# 5x5_Led_Matrix.net
KiCad netlist of a schematic drawn in EAGLE
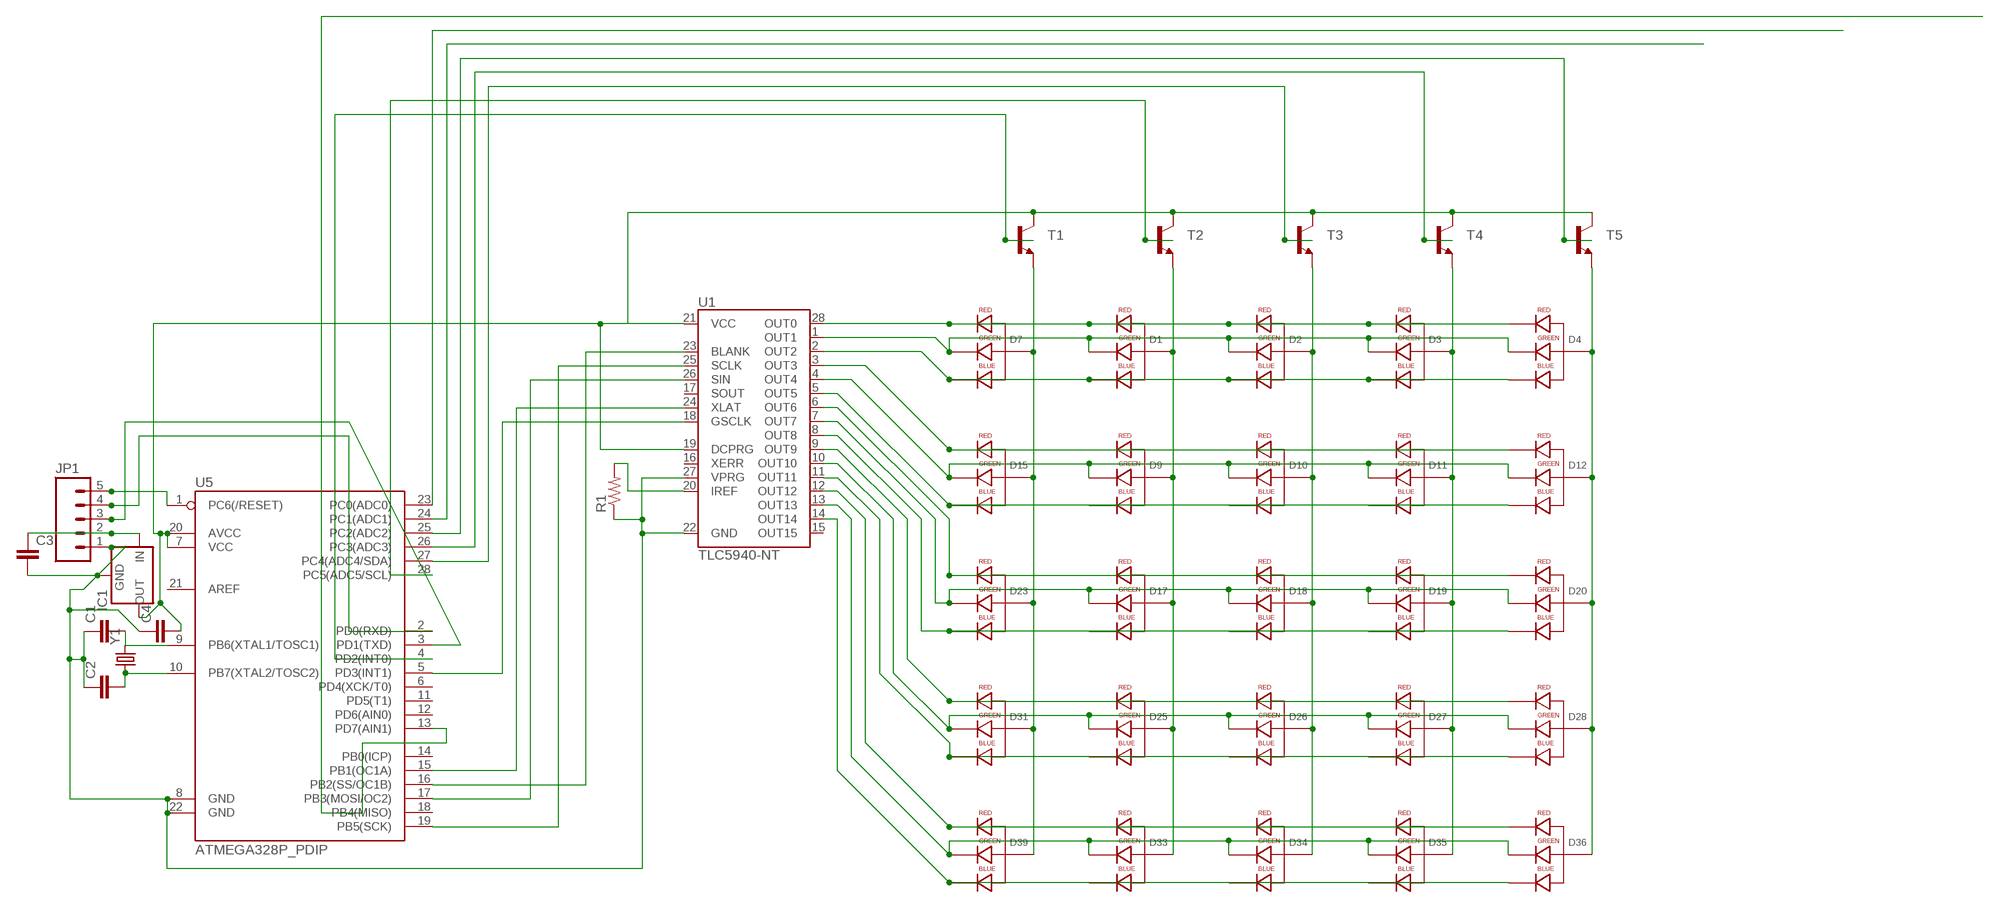
[diagram p0: schematic, sheet 1]

(export (version "E")
  (design (tool "Eeschema 10.0.6"))
  (components
    (comp (ref "C1")
      (value "CAPPTH")
      (footprint "eagle-import:CAP-PTH-SMALL")
      (libsource (lib "eagle-import") (part "CAPPTH"))
    )
    (comp (ref "C2")
      (value "CAPPTH")
      (footprint "eagle-import:CAP-PTH-SMALL")
      (libsource (lib "eagle-import") (part "CAPPTH"))
    )
    (comp (ref "C3")
      (value "CAPPTH")
      (footprint "eagle-import:CAP-PTH-SMALL")
      (libsource (lib "eagle-import") (part "SparkFun-Passives_CAPPTH"))
    )
    (comp (ref "C4")
      (value "CAPPTH")
      (footprint "eagle-import:CAP-PTH-SMALL")
      (libsource (lib "eagle-import") (part "SparkFun-Passives_CAPPTH"))
    )
    (comp (ref "D1")
      (value "LED-RGB-CA-THRUDIFFUSE")
      (footprint "eagle-import:LED-RGB-THRU")
      (libsource (lib "eagle-import") (part "LED-RGB-CA-THRUDIFFUSE"))
    )
    (comp (ref "D2")
      (value "LED-RGB-CA-THRUDIFFUSE")
      (footprint "eagle-import:LED-RGB-THRU")
      (libsource (lib "eagle-import") (part "LED-RGB-CA-THRUDIFFUSE"))
    )
    (comp (ref "D3")
      (value "LED-RGB-CA-THRUDIFFUSE")
      (footprint "eagle-import:LED-RGB-THRU")
      (libsource (lib "eagle-import") (part "LED-RGB-CA-THRUDIFFUSE"))
    )
    (comp (ref "D4")
      (value "LED-RGB-CA-THRUDIFFUSE")
      (footprint "eagle-import:LED-RGB-THRU")
      (libsource (lib "eagle-import") (part "LED-RGB-CA-THRUDIFFUSE"))
    )
    (comp (ref "D7")
      (value "LED-RGB-CA-THRUCLEAR")
      (footprint "eagle-import:LED-RGB-THRU")
      (libsource (lib "eagle-import") (part "LED-RGB-CA-THRUCLEAR"))
    )
    (comp (ref "D9")
      (value "LED-RGB-CA-THRUDIFFUSE")
      (footprint "eagle-import:LED-RGB-THRU")
      (libsource (lib "eagle-import") (part "LED-RGB-CA-THRUDIFFUSE"))
    )
    (comp (ref "D10")
      (value "LED-RGB-CA-THRUDIFFUSE")
      (footprint "eagle-import:LED-RGB-THRU")
      (libsource (lib "eagle-import") (part "LED-RGB-CA-THRUDIFFUSE"))
    )
    (comp (ref "D11")
      (value "LED-RGB-CA-THRUDIFFUSE")
      (footprint "eagle-import:LED-RGB-THRU")
      (libsource (lib "eagle-import") (part "LED-RGB-CA-THRUDIFFUSE"))
    )
    (comp (ref "D12")
      (value "LED-RGB-CA-THRUDIFFUSE")
      (footprint "eagle-import:LED-RGB-THRU")
      (libsource (lib "eagle-import") (part "LED-RGB-CA-THRUDIFFUSE"))
    )
    (comp (ref "D15")
      (value "LED-RGB-CA-THRUDIFFUSE")
      (footprint "eagle-import:LED-RGB-THRU")
      (libsource (lib "eagle-import") (part "LED-RGB-CA-THRUDIFFUSE"))
    )
    (comp (ref "D17")
      (value "LED-RGB-CA-THRUDIFFUSE")
      (footprint "eagle-import:LED-RGB-THRU")
      (libsource (lib "eagle-import") (part "LED-RGB-CA-THRUDIFFUSE"))
    )
    (comp (ref "D18")
      (value "LED-RGB-CA-THRUDIFFUSE")
      (footprint "eagle-import:LED-RGB-THRU")
      (libsource (lib "eagle-import") (part "LED-RGB-CA-THRUDIFFUSE"))
    )
    (comp (ref "D19")
      (value "LED-RGB-CA-THRUDIFFUSE")
      (footprint "eagle-import:LED-RGB-THRU")
      (libsource (lib "eagle-import") (part "LED-RGB-CA-THRUDIFFUSE"))
    )
    (comp (ref "D20")
      (value "LED-RGB-CA-THRUDIFFUSE")
      (footprint "eagle-import:LED-RGB-THRU")
      (libsource (lib "eagle-import") (part "LED-RGB-CA-THRUDIFFUSE"))
    )
    (comp (ref "D23")
      (value "LED-RGB-CA-THRUDIFFUSE")
      (footprint "eagle-import:LED-RGB-THRU")
      (libsource (lib "eagle-import") (part "LED-RGB-CA-THRUDIFFUSE"))
    )
    (comp (ref "D25")
      (value "LED-RGB-CA-THRUDIFFUSE")
      (footprint "eagle-import:LED-RGB-THRU")
      (libsource (lib "eagle-import") (part "LED-RGB-CA-THRUDIFFUSE"))
    )
    (comp (ref "D26")
      (value "LED-RGB-CA-THRUDIFFUSE")
      (footprint "eagle-import:LED-RGB-THRU")
      (libsource (lib "eagle-import") (part "LED-RGB-CA-THRUDIFFUSE"))
    )
    (comp (ref "D27")
      (value "LED-RGB-CA-THRUDIFFUSE")
      (footprint "eagle-import:LED-RGB-THRU")
      (libsource (lib "eagle-import") (part "LED-RGB-CA-THRUDIFFUSE"))
    )
    (comp (ref "D28")
      (value "LED-RGB-CA-THRUCLEAR")
      (footprint "eagle-import:LED-RGB-THRU")
      (libsource (lib "eagle-import") (part "LED-RGB-CA-THRUCLEAR"))
    )
    (comp (ref "D31")
      (value "LED-RGB-CA-THRUDIFFUSE")
      (footprint "eagle-import:LED-RGB-THRU")
      (libsource (lib "eagle-import") (part "LED-RGB-CA-THRUDIFFUSE"))
    )
    (comp (ref "D33")
      (value "LED-RGB-CA-THRUDIFFUSE")
      (footprint "eagle-import:LED-RGB-THRU")
      (libsource (lib "eagle-import") (part "LED-RGB-CA-THRUDIFFUSE"))
    )
    (comp (ref "D34")
      (value "LED-RGB-CA-THRUDIFFUSE")
      (footprint "eagle-import:LED-RGB-THRU")
      (libsource (lib "eagle-import") (part "LED-RGB-CA-THRUDIFFUSE"))
    )
    (comp (ref "D35")
      (value "LED-RGB-CA-THRUDIFFUSE")
      (footprint "eagle-import:LED-RGB-THRU")
      (libsource (lib "eagle-import") (part "LED-RGB-CA-THRUDIFFUSE"))
    )
    (comp (ref "D36")
      (value "LED-RGB-CA-THRUDIFFUSE")
      (footprint "eagle-import:LED-RGB-THRU")
      (libsource (lib "eagle-import") (part "LED-RGB-CA-THRUDIFFUSE"))
    )
    (comp (ref "D39")
      (value "LED-RGB-CA-THRUDIFFUSE")
      (footprint "eagle-import:LED-RGB-THRU")
      (libsource (lib "eagle-import") (part "LED-RGB-CA-THRUDIFFUSE"))
    )
    (comp (ref "IC1")
      (value "V_REG_78XXSIDE")
      (footprint "eagle-import:78XXL")
      (libsource (lib "eagle-import") (part "V_REG_78XXSIDE"))
    )
    (comp (ref "JP1")
      (value "M05PTH")
      (footprint "eagle-import:1X05")
      (libsource (lib "eagle-import") (part "M05PTH"))
    )
    (comp (ref "R1")
      (value "RESISTORPTH-1/2W")
      (footprint "eagle-import:AXIAL-0.5")
      (libsource (lib "eagle-import") (part "RESISTORPTH-1/2W"))
    )
    (comp (ref "T1")
      (value "TRANSISTOR_NPN2N3904")
      (footprint "eagle-import:TO-92")
      (libsource (lib "eagle-import") (part "TRANSISTOR_NPN2N3904"))
    )
    (comp (ref "T2")
      (value "TRANSISTOR_NPN2N3904")
      (footprint "eagle-import:TO-92")
      (libsource (lib "eagle-import") (part "TRANSISTOR_NPN2N3904"))
    )
    (comp (ref "T3")
      (value "TRANSISTOR_NPN2N3904")
      (footprint "eagle-import:TO-92")
      (libsource (lib "eagle-import") (part "TRANSISTOR_NPN2N3904"))
    )
    (comp (ref "T4")
      (value "TRANSISTOR_NPN2N3904")
      (footprint "eagle-import:TO-92")
      (libsource (lib "eagle-import") (part "TRANSISTOR_NPN2N3904"))
    )
    (comp (ref "T5")
      (value "TRANSISTOR_NPN2N3904")
      (footprint "eagle-import:TO-92")
      (libsource (lib "eagle-import") (part "TRANSISTOR_NPN2N3904"))
    )
    (comp (ref "U1")
      (value "TLC5940-NT")
      (footprint "eagle-import:DIL28-3")
      (libsource (lib "eagle-import") (part "TLC5940-NT"))
    )
    (comp (ref "U5")
      (value "ATMEGA328P_PDIP")
      (footprint "eagle-import:DIL28-3")
      (libsource (lib "eagle-import") (part "ATMEGA328P_PDIP"))
    )
    (comp (ref "Y1")
      (value "CRYSTALHC49US")
      (footprint "eagle-import:HC49US")
      (libsource (lib "eagle-import") (part "CRYSTALHC49US"))
    )
  )
  (nets
    (net (code "1") (name "Net-(C3-Pad1)") (class "Default")
      (node (ref "C3") (pin "1") (pinfunction "1_1") (pintype "passive"))
      (node (ref "IC1") (pin "IN") (pinfunction "IN_IN") (pintype "input"))
      (node (ref "JP1") (pin "2") (pinfunction "2_2") (pintype "passive"))
    )
    (net (code "2") (name "Net-(D1-ANODE)") (class "Default")
      (node (ref "D1") (pin "2") (pinfunction "ANODE_2") (pintype "bidirectional"))
      (node (ref "D17") (pin "2") (pinfunction "ANODE_2") (pintype "bidirectional"))
      (node (ref "D25") (pin "2") (pinfunction "ANODE_2") (pintype "bidirectional"))
      (node (ref "D33") (pin "2") (pinfunction "ANODE_2") (pintype "bidirectional"))
      (node (ref "D9") (pin "2") (pinfunction "ANODE_2") (pintype "bidirectional"))
      (node (ref "T2") (pin "1") (pinfunction "E_1") (pintype "passive"))
    )
    (net (code "3") (name "Net-(D1-BLUE_CATHODE)") (class "Default")
      (node (ref "D1") (pin "4") (pinfunction "BLUE_CATHODE_4") (pintype "bidirectional"))
      (node (ref "D2") (pin "4") (pinfunction "BLUE_CATHODE_4") (pintype "bidirectional"))
      (node (ref "D3") (pin "4") (pinfunction "BLUE_CATHODE_4") (pintype "bidirectional"))
      (node (ref "D4") (pin "4") (pinfunction "BLUE_CATHODE_4") (pintype "bidirectional"))
      (node (ref "D7") (pin "4") (pinfunction "BLUE_CATHODE_4") (pintype "bidirectional"))
      (node (ref "U1") (pin "2") (pinfunction "OUT2_2") (pintype "bidirectional"))
    )
    (net (code "4") (name "Net-(D1-GREEN_CATHODE)") (class "Default")
      (node (ref "D1") (pin "3") (pinfunction "GREEN_CATHODE_3") (pintype "bidirectional"))
      (node (ref "D2") (pin "3") (pinfunction "GREEN_CATHODE_3") (pintype "bidirectional"))
      (node (ref "D3") (pin "3") (pinfunction "GREEN_CATHODE_3") (pintype "bidirectional"))
      (node (ref "D4") (pin "3") (pinfunction "GREEN_CATHODE_3") (pintype "bidirectional"))
      (node (ref "D7") (pin "3") (pinfunction "GREEN_CATHODE_3") (pintype "bidirectional"))
      (node (ref "U1") (pin "1") (pinfunction "OUT1_1") (pintype "bidirectional"))
    )
    (net (code "5") (name "Net-(D1-RED_CATHODE)") (class "Default")
      (node (ref "D1") (pin "1") (pinfunction "RED_CATHODE_1") (pintype "bidirectional"))
      (node (ref "D2") (pin "1") (pinfunction "RED_CATHODE_1") (pintype "bidirectional"))
      (node (ref "D3") (pin "1") (pinfunction "RED_CATHODE_1") (pintype "bidirectional"))
      (node (ref "D4") (pin "1") (pinfunction "RED_CATHODE_1") (pintype "bidirectional"))
      (node (ref "D7") (pin "1") (pinfunction "RED_CATHODE_1") (pintype "bidirectional"))
      (node (ref "U1") (pin "28") (pinfunction "OUT0_28") (pintype "bidirectional"))
    )
    (net (code "6") (name "Net-(D10-ANODE)") (class "Default")
      (node (ref "D10") (pin "2") (pinfunction "ANODE_2") (pintype "bidirectional"))
      (node (ref "D18") (pin "2") (pinfunction "ANODE_2") (pintype "bidirectional"))
      (node (ref "D2") (pin "2") (pinfunction "ANODE_2") (pintype "bidirectional"))
      (node (ref "D26") (pin "2") (pinfunction "ANODE_2") (pintype "bidirectional"))
      (node (ref "D34") (pin "2") (pinfunction "ANODE_2") (pintype "bidirectional"))
      (node (ref "T3") (pin "1") (pinfunction "E_1") (pintype "passive"))
    )
    (net (code "7") (name "Net-(D10-BLUE_CATHODE)") (class "Default")
      (node (ref "D10") (pin "4") (pinfunction "BLUE_CATHODE_4") (pintype "bidirectional"))
      (node (ref "D11") (pin "4") (pinfunction "BLUE_CATHODE_4") (pintype "bidirectional"))
      (node (ref "D12") (pin "4") (pinfunction "BLUE_CATHODE_4") (pintype "bidirectional"))
      (node (ref "D15") (pin "4") (pinfunction "BLUE_CATHODE_4") (pintype "bidirectional"))
      (node (ref "D9") (pin "4") (pinfunction "BLUE_CATHODE_4") (pintype "bidirectional"))
      (node (ref "U1") (pin "5") (pinfunction "OUT5_5") (pintype "bidirectional"))
    )
    (net (code "8") (name "Net-(D10-GREEN_CATHODE)") (class "Default")
      (node (ref "D10") (pin "3") (pinfunction "GREEN_CATHODE_3") (pintype "bidirectional"))
      (node (ref "D11") (pin "3") (pinfunction "GREEN_CATHODE_3") (pintype "bidirectional"))
      (node (ref "D12") (pin "3") (pinfunction "GREEN_CATHODE_3") (pintype "bidirectional"))
      (node (ref "D15") (pin "3") (pinfunction "GREEN_CATHODE_3") (pintype "bidirectional"))
      (node (ref "D9") (pin "3") (pinfunction "GREEN_CATHODE_3") (pintype "bidirectional"))
      (node (ref "U1") (pin "4") (pinfunction "OUT4_4") (pintype "bidirectional"))
    )
    (net (code "9") (name "Net-(D10-RED_CATHODE)") (class "Default")
      (node (ref "D10") (pin "1") (pinfunction "RED_CATHODE_1") (pintype "bidirectional"))
      (node (ref "D11") (pin "1") (pinfunction "RED_CATHODE_1") (pintype "bidirectional"))
      (node (ref "D12") (pin "1") (pinfunction "RED_CATHODE_1") (pintype "bidirectional"))
      (node (ref "D15") (pin "1") (pinfunction "RED_CATHODE_1") (pintype "bidirectional"))
      (node (ref "D9") (pin "1") (pinfunction "RED_CATHODE_1") (pintype "bidirectional"))
      (node (ref "U1") (pin "3") (pinfunction "OUT3_3") (pintype "bidirectional"))
    )
    (net (code "10") (name "Net-(D11-ANODE)") (class "Default")
      (node (ref "D11") (pin "2") (pinfunction "ANODE_2") (pintype "bidirectional"))
      (node (ref "D19") (pin "2") (pinfunction "ANODE_2") (pintype "bidirectional"))
      (node (ref "D27") (pin "2") (pinfunction "ANODE_2") (pintype "bidirectional"))
      (node (ref "D3") (pin "2") (pinfunction "ANODE_2") (pintype "bidirectional"))
      (node (ref "D35") (pin "2") (pinfunction "ANODE_2") (pintype "bidirectional"))
      (node (ref "T4") (pin "1") (pinfunction "E_1") (pintype "passive"))
    )
    (net (code "11") (name "Net-(D12-ANODE)") (class "Default")
      (node (ref "D12") (pin "2") (pinfunction "ANODE_2") (pintype "bidirectional"))
      (node (ref "D20") (pin "2") (pinfunction "ANODE_2") (pintype "bidirectional"))
      (node (ref "D28") (pin "2") (pinfunction "ANODE_2") (pintype "bidirectional"))
      (node (ref "D36") (pin "2") (pinfunction "ANODE_2") (pintype "bidirectional"))
      (node (ref "D4") (pin "2") (pinfunction "ANODE_2") (pintype "bidirectional"))
      (node (ref "T5") (pin "1") (pinfunction "E_1") (pintype "passive"))
    )
    (net (code "12") (name "Net-(D15-ANODE)") (class "Default")
      (node (ref "D15") (pin "2") (pinfunction "ANODE_2") (pintype "bidirectional"))
      (node (ref "D23") (pin "2") (pinfunction "ANODE_2") (pintype "bidirectional"))
      (node (ref "D31") (pin "2") (pinfunction "ANODE_2") (pintype "bidirectional"))
      (node (ref "D39") (pin "2") (pinfunction "ANODE_2") (pintype "bidirectional"))
      (node (ref "D7") (pin "2") (pinfunction "ANODE_2") (pintype "bidirectional"))
      (node (ref "T1") (pin "1") (pinfunction "E_1") (pintype "passive"))
    )
    (net (code "13") (name "Net-(D17-BLUE_CATHODE)") (class "Default")
      (node (ref "D17") (pin "4") (pinfunction "BLUE_CATHODE_4") (pintype "bidirectional"))
      (node (ref "D18") (pin "4") (pinfunction "BLUE_CATHODE_4") (pintype "bidirectional"))
      (node (ref "D19") (pin "4") (pinfunction "BLUE_CATHODE_4") (pintype "bidirectional"))
      (node (ref "D20") (pin "4") (pinfunction "BLUE_CATHODE_4") (pintype "bidirectional"))
      (node (ref "D23") (pin "4") (pinfunction "BLUE_CATHODE_4") (pintype "bidirectional"))
      (node (ref "U1") (pin "8") (pinfunction "OUT8_8") (pintype "bidirectional"))
    )
    (net (code "14") (name "Net-(D17-GREEN_CATHODE)") (class "Default")
      (node (ref "D17") (pin "3") (pinfunction "GREEN_CATHODE_3") (pintype "bidirectional"))
      (node (ref "D18") (pin "3") (pinfunction "GREEN_CATHODE_3") (pintype "bidirectional"))
      (node (ref "D19") (pin "3") (pinfunction "GREEN_CATHODE_3") (pintype "bidirectional"))
      (node (ref "D20") (pin "3") (pinfunction "GREEN_CATHODE_3") (pintype "bidirectional"))
      (node (ref "D23") (pin "3") (pinfunction "GREEN_CATHODE_3") (pintype "bidirectional"))
      (node (ref "U1") (pin "7") (pinfunction "OUT7_7") (pintype "bidirectional"))
    )
    (net (code "15") (name "Net-(D17-RED_CATHODE)") (class "Default")
      (node (ref "D17") (pin "1") (pinfunction "RED_CATHODE_1") (pintype "bidirectional"))
      (node (ref "D18") (pin "1") (pinfunction "RED_CATHODE_1") (pintype "bidirectional"))
      (node (ref "D19") (pin "1") (pinfunction "RED_CATHODE_1") (pintype "bidirectional"))
      (node (ref "D20") (pin "1") (pinfunction "RED_CATHODE_1") (pintype "bidirectional"))
      (node (ref "D23") (pin "1") (pinfunction "RED_CATHODE_1") (pintype "bidirectional"))
      (node (ref "U1") (pin "6") (pinfunction "OUT6_6") (pintype "bidirectional"))
    )
    (net (code "16") (name "Net-(D25-BLUE_CATHODE)") (class "Default")
      (node (ref "D25") (pin "4") (pinfunction "BLUE_CATHODE_4") (pintype "bidirectional"))
      (node (ref "D26") (pin "4") (pinfunction "BLUE_CATHODE_4") (pintype "bidirectional"))
      (node (ref "D27") (pin "4") (pinfunction "BLUE_CATHODE_4") (pintype "bidirectional"))
      (node (ref "D28") (pin "4") (pinfunction "BLUE_CATHODE_4") (pintype "bidirectional"))
      (node (ref "D31") (pin "4") (pinfunction "BLUE_CATHODE_4") (pintype "bidirectional"))
      (node (ref "U1") (pin "11") (pinfunction "OUT11_11") (pintype "bidirectional"))
    )
    (net (code "17") (name "Net-(D25-GREEN_CATHODE)") (class "Default")
      (node (ref "D25") (pin "3") (pinfunction "GREEN_CATHODE_3") (pintype "bidirectional"))
      (node (ref "D26") (pin "3") (pinfunction "GREEN_CATHODE_3") (pintype "bidirectional"))
      (node (ref "D27") (pin "3") (pinfunction "GREEN_CATHODE_3") (pintype "bidirectional"))
      (node (ref "D28") (pin "3") (pinfunction "GREEN_CATHODE_3") (pintype "bidirectional"))
      (node (ref "D31") (pin "3") (pinfunction "GREEN_CATHODE_3") (pintype "bidirectional"))
      (node (ref "U1") (pin "10") (pinfunction "OUT10_10") (pintype "bidirectional"))
    )
    (net (code "18") (name "Net-(D25-RED_CATHODE)") (class "Default")
      (node (ref "D25") (pin "1") (pinfunction "RED_CATHODE_1") (pintype "bidirectional"))
      (node (ref "D26") (pin "1") (pinfunction "RED_CATHODE_1") (pintype "bidirectional"))
      (node (ref "D27") (pin "1") (pinfunction "RED_CATHODE_1") (pintype "bidirectional"))
      (node (ref "D28") (pin "1") (pinfunction "RED_CATHODE_1") (pintype "bidirectional"))
      (node (ref "D31") (pin "1") (pinfunction "RED_CATHODE_1") (pintype "bidirectional"))
      (node (ref "U1") (pin "9") (pinfunction "OUT9_9") (pintype "bidirectional"))
    )
    (net (code "19") (name "Net-(D33-BLUE_CATHODE)") (class "Default")
      (node (ref "D33") (pin "4") (pinfunction "BLUE_CATHODE_4") (pintype "bidirectional"))
      (node (ref "D34") (pin "4") (pinfunction "BLUE_CATHODE_4") (pintype "bidirectional"))
      (node (ref "D35") (pin "4") (pinfunction "BLUE_CATHODE_4") (pintype "bidirectional"))
      (node (ref "D36") (pin "4") (pinfunction "BLUE_CATHODE_4") (pintype "bidirectional"))
      (node (ref "D39") (pin "4") (pinfunction "BLUE_CATHODE_4") (pintype "bidirectional"))
      (node (ref "U1") (pin "14") (pinfunction "OUT14_14") (pintype "bidirectional"))
    )
    (net (code "20") (name "Net-(D33-GREEN_CATHODE)") (class "Default")
      (node (ref "D33") (pin "3") (pinfunction "GREEN_CATHODE_3") (pintype "bidirectional"))
      (node (ref "D34") (pin "3") (pinfunction "GREEN_CATHODE_3") (pintype "bidirectional"))
      (node (ref "D35") (pin "3") (pinfunction "GREEN_CATHODE_3") (pintype "bidirectional"))
      (node (ref "D36") (pin "3") (pinfunction "GREEN_CATHODE_3") (pintype "bidirectional"))
      (node (ref "D39") (pin "3") (pinfunction "GREEN_CATHODE_3") (pintype "bidirectional"))
      (node (ref "U1") (pin "13") (pinfunction "OUT13_13") (pintype "bidirectional"))
    )
    (net (code "21") (name "Net-(D33-RED_CATHODE)") (class "Default")
      (node (ref "D33") (pin "1") (pinfunction "RED_CATHODE_1") (pintype "bidirectional"))
      (node (ref "D34") (pin "1") (pinfunction "RED_CATHODE_1") (pintype "bidirectional"))
      (node (ref "D35") (pin "1") (pinfunction "RED_CATHODE_1") (pintype "bidirectional"))
      (node (ref "D36") (pin "1") (pinfunction "RED_CATHODE_1") (pintype "bidirectional"))
      (node (ref "D39") (pin "1") (pinfunction "RED_CATHODE_1") (pintype "bidirectional"))
      (node (ref "U1") (pin "12") (pinfunction "OUT12_12") (pintype "bidirectional"))
    )
    (net (code "22") (name "Net-(R1-1)") (class "Default")
      (node (ref "C1") (pin "1") (pinfunction "1_1") (pintype "passive"))
      (node (ref "C2") (pin "1") (pinfunction "1_1") (pintype "passive"))
      (node (ref "C3") (pin "2") (pinfunction "2_2") (pintype "passive"))
      (node (ref "C4") (pin "1") (pinfunction "1_1") (pintype "passive"))
      (node (ref "IC1") (pin "GND") (pinfunction "GND_GND") (pintype "input"))
      (node (ref "JP1") (pin "1") (pinfunction "1_1") (pintype "passive"))
      (node (ref "R1") (pin "P$1") (pinfunction "1_P$1") (pintype "passive"))
      (node (ref "U1") (pin "22") (pinfunction "GND_22") (pintype "bidirectional"))
      (node (ref "U1") (pin "27") (pinfunction "VPRG_27") (pintype "bidirectional"))
      (node (ref "U5") (pin "22") (pinfunction "GND_22") (pintype "bidirectional"))
      (node (ref "U5") (pin "8") (pinfunction "GND_8") (pintype "bidirectional"))
    )
    (net (code "23") (name "Net-(R1-2)") (class "Default")
      (node (ref "R1") (pin "P$2") (pinfunction "2_P$2") (pintype "passive"))
      (node (ref "U1") (pin "20") (pinfunction "IREF_20") (pintype "bidirectional"))
    )
    (net (code "24") (name "Net-(T1-B)") (class "Default")
      (node (ref "T1") (pin "2") (pinfunction "B_2") (pintype "passive"))
      (node (ref "U5") (pin "4") (pinfunction "PD2(INT0)_4") (pintype "bidirectional"))
    )
    (net (code "25") (name "Net-(T1-C)") (class "Default")
      (node (ref "C4") (pin "2") (pinfunction "2_2") (pintype "passive"))
      (node (ref "IC1") (pin "OUT") (pinfunction "OUT_OUT") (pintype "output"))
      (node (ref "T1") (pin "3") (pinfunction "C_3") (pintype "passive"))
      (node (ref "T2") (pin "3") (pinfunction "C_3") (pintype "passive"))
      (node (ref "T3") (pin "3") (pinfunction "C_3") (pintype "passive"))
      (node (ref "T4") (pin "3") (pinfunction "C_3") (pintype "passive"))
      (node (ref "T5") (pin "3") (pinfunction "C_3") (pintype "passive"))
      (node (ref "U1") (pin "19") (pinfunction "DCPRG_19") (pintype "bidirectional"))
      (node (ref "U1") (pin "21") (pinfunction "VCC_21") (pintype "bidirectional"))
      (node (ref "U5") (pin "20") (pinfunction "AVCC_20") (pintype "bidirectional"))
      (node (ref "U5") (pin "7") (pinfunction "VCC_7") (pintype "bidirectional"))
    )
    (net (code "26") (name "Net-(T2-B)") (class "Default")
      (node (ref "T2") (pin "2") (pinfunction "B_2") (pintype "passive"))
      (node (ref "U5") (pin "28") (pinfunction "PC5(ADC5/SCL)_28") (pintype "bidirectional"))
    )
    (net (code "27") (name "Net-(T3-B)") (class "Default")
      (node (ref "T3") (pin "2") (pinfunction "B_2") (pintype "passive"))
      (node (ref "U5") (pin "27") (pinfunction "PC4(ADC4/SDA)_27") (pintype "bidirectional"))
    )
    (net (code "28") (name "Net-(T4-B)") (class "Default")
      (node (ref "T4") (pin "2") (pinfunction "B_2") (pintype "passive"))
      (node (ref "U5") (pin "26") (pinfunction "PC3(ADC3)_26") (pintype "bidirectional"))
    )
    (net (code "29") (name "Net-(T5-B)") (class "Default")
      (node (ref "T5") (pin "2") (pinfunction "B_2") (pintype "passive"))
      (node (ref "U5") (pin "25") (pinfunction "PC2(ADC2)_25") (pintype "bidirectional"))
    )
    (net (code "30") (name "Net-(U1-BLANK)") (class "Default")
      (node (ref "U1") (pin "23") (pinfunction "BLANK_23") (pintype "bidirectional"))
      (node (ref "U5") (pin "16") (pinfunction "PB2(SS/OC1B)_16") (pintype "bidirectional"))
    )
    (net (code "31") (name "Net-(U1-GSCLK)") (class "Default")
      (node (ref "U1") (pin "18") (pinfunction "GSCLK_18") (pintype "bidirectional"))
      (node (ref "U5") (pin "5") (pinfunction "PD3(INT1)_5") (pintype "bidirectional"))
    )
    (net (code "32") (name "Net-(U1-SCLK)") (class "Default")
      (node (ref "U1") (pin "25") (pinfunction "SCLK_25") (pintype "bidirectional"))
      (node (ref "U5") (pin "19") (pinfunction "PB5(SCK)_19") (pintype "bidirectional"))
    )
    (net (code "33") (name "Net-(U1-SIN)") (class "Default")
      (node (ref "U1") (pin "26") (pinfunction "SIN_26") (pintype "bidirectional"))
      (node (ref "U5") (pin "17") (pinfunction "PB3(MOSI/OC2)_17") (pintype "bidirectional"))
    )
    (net (code "34") (name "Net-(U1-XLAT)") (class "Default")
      (node (ref "U1") (pin "24") (pinfunction "XLAT_24") (pintype "bidirectional"))
      (node (ref "U5") (pin "15") (pinfunction "PB1(OC1A)_15") (pintype "bidirectional"))
    )
    (net (code "35") (name "Net-(U5-PB6(XTAL1{slash}TOSC1))") (class "Default")
      (node (ref "C1") (pin "2") (pinfunction "2_2") (pintype "passive"))
      (node (ref "U5") (pin "9") (pinfunction "PB6(XTAL1/TOSC1)_9") (pintype "bidirectional"))
      (node (ref "Y1") (pin "2") (pinfunction "2_2") (pintype "passive"))
    )
    (net (code "36") (name "Net-(U5-PB7(XTAL2{slash}TOSC2))") (class "Default")
      (node (ref "C2") (pin "2") (pinfunction "2_2") (pintype "passive"))
      (node (ref "U5") (pin "10") (pinfunction "PB7(XTAL2/TOSC2)_10") (pintype "bidirectional"))
      (node (ref "Y1") (pin "1") (pinfunction "1_1") (pintype "passive"))
    )
    (net (code "37") (name "Net-(U5-PC6({slash}RESET))") (class "Default")
      (node (ref "JP1") (pin "5") (pinfunction "5_5") (pintype "passive"))
      (node (ref "U5") (pin "1") (pinfunction "PC6(/RESET)_1") (pintype "bidirectional"))
    )
    (net (code "38") (name "Net-(U5-PD0(RXD))") (class "Default")
      (node (ref "JP1") (pin "4") (pinfunction "4_4") (pintype "passive"))
      (node (ref "U5") (pin "2") (pinfunction "PD0(RXD)_2") (pintype "bidirectional"))
    )
    (net (code "39") (name "Net-(U5-PD1(TXD))") (class "Default")
      (node (ref "JP1") (pin "3") (pinfunction "3_3") (pintype "passive"))
      (node (ref "U5") (pin "3") (pinfunction "PD1(TXD)_3") (pintype "bidirectional"))
    )
    (net (code "40") (name "unconnected-(U1-OUT15-Pad15)") (class "Default")
      (node (ref "U1") (pin "15") (pinfunction "OUT15_15") (pintype "bidirectional"))
    )
    (net (code "41") (name "unconnected-(U1-SOUT-Pad17)") (class "Default")
      (node (ref "U1") (pin "17") (pinfunction "SOUT_17") (pintype "bidirectional"))
    )
    (net (code "42") (name "unconnected-(U1-XERR-Pad16)") (class "Default")
      (node (ref "U1") (pin "16") (pinfunction "XERR_16") (pintype "bidirectional"))
    )
    (net (code "43") (name "unconnected-(U5-AREF-Pad21)") (class "Default")
      (node (ref "U5") (pin "21") (pinfunction "AREF_21") (pintype "bidirectional"))
    )
    (net (code "44") (name "unconnected-(U5-PB0(ICP)-Pad14)") (class "Default")
      (node (ref "U5") (pin "14") (pinfunction "PB0(ICP)_14") (pintype "bidirectional"))
    )
    (net (code "45") (name "unconnected-(U5-PB4(MISO)-Pad18)") (class "Default")
      (node (ref "U5") (pin "18") (pinfunction "PB4(MISO)_18") (pintype "bidirectional"))
    )
    (net (code "46") (name "unconnected-(U5-PC0(ADC0)-Pad23)") (class "Default")
      (node (ref "U5") (pin "23") (pinfunction "PC0(ADC0)_23") (pintype "bidirectional"))
    )
    (net (code "47") (name "unconnected-(U5-PC1(ADC1)-Pad24)") (class "Default")
      (node (ref "U5") (pin "24") (pinfunction "PC1(ADC1)_24") (pintype "bidirectional"))
    )
    (net (code "48") (name "unconnected-(U5-PD4(XCK{slash}T0)-Pad6)") (class "Default")
      (node (ref "U5") (pin "6") (pinfunction "PD4(XCK/T0)_6") (pintype "bidirectional"))
    )
    (net (code "49") (name "unconnected-(U5-PD5(T1)-Pad11)") (class "Default")
      (node (ref "U5") (pin "11") (pinfunction "PD5(T1)_11") (pintype "bidirectional"))
    )
    (net (code "50") (name "unconnected-(U5-PD6(AIN0)-Pad12)") (class "Default")
      (node (ref "U5") (pin "12") (pinfunction "PD6(AIN0)_12") (pintype "bidirectional"))
    )
    (net (code "51") (name "unconnected-(U5-PD7(AIN1)-Pad13)") (class "Default")
      (node (ref "U5") (pin "13") (pinfunction "PD7(AIN1)_13") (pintype "bidirectional"))
    )
  )
)
